# so08.net
KiCad netlist of a schematic drawn in EAGLE
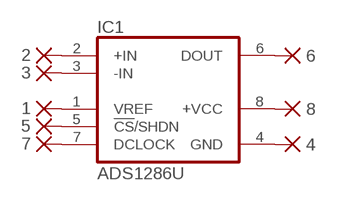
[diagram p0: schematic, sheet 1]

(export (version "E")
  (design (tool "Eeschema 10.0.6"))
  (components
    (comp (ref "1")
      (value "PAD-0360")
      (footprint "eagle-import:0360")
      (libsource (lib "eagle-import") (part "PAD-0360"))
    )
    (comp (ref "2")
      (value "PAD-0360")
      (footprint "eagle-import:0360")
      (libsource (lib "eagle-import") (part "PAD-0360"))
    )
    (comp (ref "3")
      (value "PAD-0360")
      (footprint "eagle-import:0360")
      (libsource (lib "eagle-import") (part "PAD-0360"))
    )
    (comp (ref "4")
      (value "PAD-0360")
      (footprint "eagle-import:0360")
      (libsource (lib "eagle-import") (part "PAD-0360"))
    )
    (comp (ref "5")
      (value "PAD-0360")
      (footprint "eagle-import:0360")
      (libsource (lib "eagle-import") (part "PAD-0360"))
    )
    (comp (ref "6")
      (value "PAD-0360")
      (footprint "eagle-import:0360")
      (libsource (lib "eagle-import") (part "PAD-0360"))
    )
    (comp (ref "7")
      (value "PAD-0360")
      (footprint "eagle-import:0360")
      (libsource (lib "eagle-import") (part "PAD-0360"))
    )
    (comp (ref "8")
      (value "PAD-0360")
      (footprint "eagle-import:0360")
      (libsource (lib "eagle-import") (part "PAD-0360"))
    )
    (comp (ref "IC1")
      (value "ADS1286U")
      (footprint "eagle-import:SO08")
      (fields (field (name "MF") "TEXAS INSTRUMENTS"))
      (libsource (lib "eagle-import") (part "ADS1286U"))
    )
  )
  (nets
    (net (code "1") (name "Net-(1-P)") (class "Default")
      (node (ref "1") (pin "P$1") (pinfunction "P_P$1") (pintype "passive"))
      (node (ref "IC1") (pin "1") (pinfunction "VREF_1") (pintype "input"))
    )
    (net (code "2") (name "Net-(2-P)") (class "Default")
      (node (ref "2") (pin "P$1") (pinfunction "P_P$1") (pintype "passive"))
      (node (ref "IC1") (pin "2") (pinfunction "+IN_2") (pintype "input"))
    )
    (net (code "3") (name "Net-(3-P)") (class "Default")
      (node (ref "3") (pin "P$1") (pinfunction "P_P$1") (pintype "passive"))
      (node (ref "IC1") (pin "3") (pinfunction "-IN_3") (pintype "input"))
    )
    (net (code "4") (name "Net-(4-P)") (class "Default")
      (node (ref "4") (pin "P$1") (pinfunction "P_P$1") (pintype "passive"))
      (node (ref "IC1") (pin "4") (pinfunction "GND_4") (pintype "power_in"))
    )
    (net (code "5") (name "Net-(5-P)") (class "Default")
      (node (ref "5") (pin "P$1") (pinfunction "P_P$1") (pintype "passive"))
      (node (ref "IC1") (pin "5") (pinfunction "~{CS}/SHDN_5") (pintype "input"))
    )
    (net (code "6") (name "Net-(6-P)") (class "Default")
      (node (ref "6") (pin "P$1") (pinfunction "P_P$1") (pintype "passive"))
      (node (ref "IC1") (pin "6") (pinfunction "DOUT_6") (pintype "output"))
    )
    (net (code "7") (name "Net-(7-P)") (class "Default")
      (node (ref "7") (pin "P$1") (pinfunction "P_P$1") (pintype "passive"))
      (node (ref "IC1") (pin "7") (pinfunction "DCLOCK_7") (pintype "input"))
    )
    (net (code "8") (name "Net-(8-P)") (class "Default")
      (node (ref "8") (pin "P$1") (pinfunction "P_P$1") (pintype "passive"))
      (node (ref "IC1") (pin "8") (pinfunction "+VCC_8") (pintype "power_in"))
    )
  )
)
